# instrumentation_amplifier.net
KiCad netlist of a schematic drawn in EAGLE
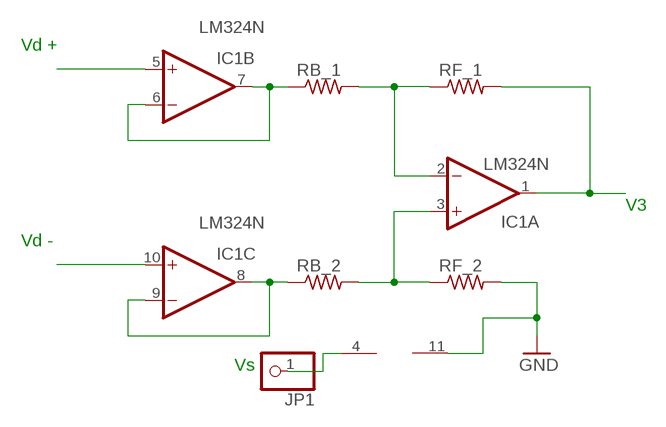
[diagram p0: schematic, sheet 1]

(export (version "E")
  (design (tool "Eeschema 10.0.6"))
  (components
    (comp (ref "IC1")
      (value "LM324N")
      (footprint "eagle-import:DIL14")
      (libsource (lib "eagle-import") (part "LM324N"))
    )
    (comp (ref "JP1")
      (value "PINHD-1X1")
      (footprint "eagle-import:1X01")
      (libsource (lib "eagle-import") (part "PINHD-1X1"))
    )
    (comp (ref "RB_1")
      (value "R-US_0309/10")
      (footprint "eagle-import:0309_10")
      (libsource (lib "eagle-import") (part "R-US_0309/10"))
    )
    (comp (ref "RB_2")
      (value "R-US_0309/10")
      (footprint "eagle-import:0309_10")
      (libsource (lib "eagle-import") (part "R-US_0309/10"))
    )
    (comp (ref "RF_1")
      (value "R-US_0309/10")
      (footprint "eagle-import:0309_10")
      (libsource (lib "eagle-import") (part "R-US_0309/10"))
    )
    (comp (ref "RF_2")
      (value "R-US_0309/10")
      (footprint "eagle-import:0309_10")
      (libsource (lib "eagle-import") (part "R-US_0309/10"))
    )
  )
  (nets
    (net (code "1") (name "GND") (class "Default")
      (node (ref "IC1") (pin "11") (pinfunction "V-_11") (pintype "power_in"))
      (node (ref "RF_2") (pin "2") (pinfunction "2_2") (pintype "passive"))
    )
    (net (code "2") (name "Net-(IC1A-+IN)") (class "Default")
      (node (ref "IC1") (pin "3") (pinfunction "+IN_3") (pintype "input"))
      (node (ref "RB_2") (pin "2") (pinfunction "2_2") (pintype "passive"))
      (node (ref "RF_2") (pin "1") (pinfunction "1_1") (pintype "passive"))
    )
    (net (code "3") (name "Net-(IC1A--IN)") (class "Default")
      (node (ref "IC1") (pin "2") (pinfunction "-IN_2") (pintype "input"))
      (node (ref "RB_1") (pin "2") (pinfunction "2_2") (pintype "passive"))
      (node (ref "RF_1") (pin "1") (pinfunction "1_1") (pintype "passive"))
    )
    (net (code "4") (name "Net-(IC1A-OUT)") (class "Default")
      (node (ref "IC1") (pin "1") (pinfunction "OUT_1") (pintype "output"))
      (node (ref "RF_1") (pin "2") (pinfunction "2_2") (pintype "passive"))
    )
    (net (code "5") (name "Net-(IC1B--IN)") (class "Default")
      (node (ref "IC1") (pin "6") (pinfunction "-IN_6") (pintype "input"))
      (node (ref "IC1") (pin "7") (pinfunction "OUT_7") (pintype "output"))
      (node (ref "RB_1") (pin "1") (pinfunction "1_1") (pintype "passive"))
    )
    (net (code "6") (name "Net-(IC1C--IN)") (class "Default")
      (node (ref "IC1") (pin "8") (pinfunction "OUT_8") (pintype "output"))
      (node (ref "IC1") (pin "9") (pinfunction "-IN_9") (pintype "input"))
      (node (ref "RB_2") (pin "1") (pinfunction "1_1") (pintype "passive"))
    )
    (net (code "7") (name "Net-(IC1E-V+)") (class "Default")
      (node (ref "IC1") (pin "4") (pinfunction "V+_4") (pintype "power_in"))
      (node (ref "JP1") (pin "1") (pinfunction "1_1") (pintype "passive"))
    )
    (net (code "8") (name "unconnected-(IC1B-+IN-Pad5)") (class "Default")
      (node (ref "IC1") (pin "5") (pinfunction "+IN_5") (pintype "input"))
    )
    (net (code "9") (name "unconnected-(IC1C-+IN-Pad10)") (class "Default")
      (node (ref "IC1") (pin "10") (pinfunction "+IN_10") (pintype "input"))
    )
  )
)
